# ReflowWiring.net
KiCad netlist of a schematic drawn in EAGLE
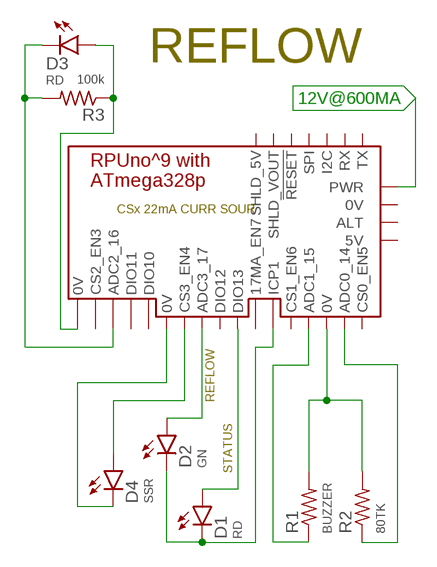
[diagram p0: schematic, sheet 1]

(export (version "E")
  (design (tool "Eeschema 10.0.6"))
  (components
    (comp (ref "BM1")
      (value "RPUNO")
      (footprint "eagle-import:NA-30")
      (libsource (lib "eagle-import") (part "RPUNO"))
    )
    (comp (ref "D1")
      (value "RD")
      (footprint "eagle-import:LED5MM")
      (libsource (lib "eagle-import") (part "LED5MM"))
    )
    (comp (ref "D2")
      (value "GN")
      (footprint "eagle-import:LED5MM")
      (libsource (lib "eagle-import") (part "LED5MM"))
    )
    (comp (ref "D3")
      (value "RD")
      (footprint "eagle-import:LED5MM")
      (libsource (lib "eagle-import") (part "LED5MM"))
    )
    (comp (ref "D4")
      (value "SSR")
      (footprint "eagle-import:LED5MM")
      (libsource (lib "eagle-import") (part "LED5MM"))
    )
    (comp (ref "R1")
      (value "BUZZER")
      (footprint "eagle-import:C0805(2012)")
      (libsource (lib "eagle-import") (part "R0805"))
    )
    (comp (ref "R2")
      (value "80TK")
      (footprint "eagle-import:C0805(2012)")
      (libsource (lib "eagle-import") (part "R0805"))
    )
    (comp (ref "R3")
      (value "100k")
      (footprint "eagle-import:C0805(2012)")
      (libsource (lib "eagle-import") (part "R0805"))
    )
  )
  (nets
    (net (code "1") (name "12V@600MA") (class "Default")
      (node (ref "BM1") (pin "8") (pinfunction "PWR_8") (pintype "bidirectional"))
    )
    (net (code "2") (name "Net-(BM1-0V-Pad26)") (class "Default")
      (node (ref "BM1") (pin "26") (pinfunction "0V_26") (pintype "bidirectional"))
      (node (ref "R1") (pin "2") (pinfunction "2_2") (pintype "passive"))
      (node (ref "R2") (pin "2") (pinfunction "2_2") (pintype "passive"))
    )
    (net (code "3") (name "Net-(BM1-0V-Pad27)") (class "Default")
      (node (ref "BM1") (pin "27") (pinfunction "0V_27") (pintype "bidirectional"))
      (node (ref "D3") (pin "A") (pinfunction "A_A") (pintype "passive"))
      (node (ref "R3") (pin "1") (pinfunction "1_1") (pintype "passive"))
    )
    (net (code "4") (name "Net-(BM1-0V-Pad28)") (class "Default")
      (node (ref "BM1") (pin "28") (pinfunction "0V_28") (pintype "bidirectional"))
      (node (ref "D4") (pin "K") (pinfunction "K_K") (pintype "passive"))
    )
    (net (code "5") (name "Net-(BM1-ADC0_14)") (class "Default")
      (node (ref "BM1") (pin "11") (pinfunction "ADC0_14_11") (pintype "bidirectional"))
      (node (ref "R2") (pin "1") (pinfunction "1_1") (pintype "passive"))
    )
    (net (code "6") (name "Net-(BM1-ADC1_15)") (class "Default")
      (node (ref "BM1") (pin "10") (pinfunction "ADC1_15_10") (pintype "bidirectional"))
      (node (ref "R1") (pin "1") (pinfunction "1_1") (pintype "passive"))
    )
    (net (code "7") (name "Net-(BM1-ADC2_16)") (class "Default")
      (node (ref "BM1") (pin "13") (pinfunction "ADC2_16_13") (pintype "bidirectional"))
      (node (ref "D3") (pin "K") (pinfunction "K_K") (pintype "passive"))
      (node (ref "R3") (pin "2") (pinfunction "2_2") (pintype "passive"))
    )
    (net (code "8") (name "Net-(BM1-ADC3_17)") (class "Default")
      (node (ref "BM1") (pin "16") (pinfunction "ADC3_17_16") (pintype "bidirectional"))
      (node (ref "D2") (pin "A") (pinfunction "A_A") (pintype "passive"))
    )
    (net (code "9") (name "Net-(BM1-CS3_EN4)") (class "Default")
      (node (ref "BM1") (pin "29") (pinfunction "CS3_EN4_29") (pintype "bidirectional"))
      (node (ref "D4") (pin "A") (pinfunction "A_A") (pintype "passive"))
    )
    (net (code "10") (name "Net-(BM1-DIO13)") (class "Default")
      (node (ref "BM1") (pin "18") (pinfunction "DIO13_18") (pintype "bidirectional"))
      (node (ref "D1") (pin "A") (pinfunction "A_A") (pintype "passive"))
    )
    (net (code "11") (name "Net-(BM1-ICP1)") (class "Default")
      (node (ref "BM1") (pin "12") (pinfunction "ICP1_12") (pintype "bidirectional"))
      (node (ref "D1") (pin "K") (pinfunction "K_K") (pintype "passive"))
      (node (ref "D2") (pin "K") (pinfunction "K_K") (pintype "passive"))
    )
    (net (code "12") (name "unconnected-(BM1-0V-Pad9)") (class "Default")
      (node (ref "BM1") (pin "9") (pinfunction "0V_9") (pintype "bidirectional"))
    )
    (net (code "13") (name "unconnected-(BM1-5V-Pad19)") (class "Default")
      (node (ref "BM1") (pin "19") (pinfunction "5V_19") (pintype "bidirectional"))
    )
    (net (code "14") (name "unconnected-(BM1-17MA_EN7-Pad21)") (class "Default")
      (node (ref "BM1") (pin "21") (pinfunction "17MA_EN7_21") (pintype "bidirectional"))
    )
    (net (code "15") (name "unconnected-(BM1-ALT-Pad20)") (class "Default")
      (node (ref "BM1") (pin "20") (pinfunction "ALT_20") (pintype "bidirectional"))
    )
    (net (code "16") (name "unconnected-(BM1-CS0_EN5-Pad23)") (class "Default")
      (node (ref "BM1") (pin "23") (pinfunction "CS0_EN5_23") (pintype "bidirectional"))
    )
    (net (code "17") (name "unconnected-(BM1-CS1_EN6-Pad22)") (class "Default")
      (node (ref "BM1") (pin "22") (pinfunction "CS1_EN6_22") (pintype "bidirectional"))
    )
    (net (code "18") (name "unconnected-(BM1-CS2_EN3-Pad24)") (class "Default")
      (node (ref "BM1") (pin "24") (pinfunction "CS2_EN3_24") (pintype "bidirectional"))
    )
    (net (code "19") (name "unconnected-(BM1-DIO10-Pad15)") (class "Default")
      (node (ref "BM1") (pin "15") (pinfunction "DIO10_15") (pintype "bidirectional"))
    )
    (net (code "20") (name "unconnected-(BM1-DIO11-Pad14)") (class "Default")
      (node (ref "BM1") (pin "14") (pinfunction "DIO11_14") (pintype "bidirectional"))
    )
    (net (code "21") (name "unconnected-(BM1-DIO12-Pad17)") (class "Default")
      (node (ref "BM1") (pin "17") (pinfunction "DIO12_17") (pintype "bidirectional"))
    )
    (net (code "22") (name "unconnected-(BM1-I2C-Pad3)") (class "Default")
      (node (ref "BM1") (pin "3") (pinfunction "I2C_3") (pintype "bidirectional"))
    )
    (net (code "23") (name "unconnected-(BM1-RX-Pad2)") (class "Default")
      (node (ref "BM1") (pin "2") (pinfunction "RX_2") (pintype "bidirectional"))
    )
    (net (code "24") (name "unconnected-(BM1-SHLD_5V-Pad6)") (class "Default")
      (node (ref "BM1") (pin "6") (pinfunction "SHLD_5V_6") (pintype "bidirectional"))
    )
    (net (code "25") (name "unconnected-(BM1-SHLD_VOUT-Pad7)") (class "Default")
      (node (ref "BM1") (pin "7") (pinfunction "SHLD_VOUT_7") (pintype "bidirectional"))
    )
    (net (code "26") (name "unconnected-(BM1-SPI-Pad4)") (class "Default")
      (node (ref "BM1") (pin "4") (pinfunction "SPI_4") (pintype "bidirectional"))
    )
    (net (code "27") (name "unconnected-(BM1-TX-Pad1)") (class "Default")
      (node (ref "BM1") (pin "1") (pinfunction "TX_1") (pintype "bidirectional"))
    )
    (net (code "28") (name "unconnected-(BM1-~{RESET}-Pad5)") (class "Default")
      (node (ref "BM1") (pin "5") (pinfunction "~{RESET}_5") (pintype "bidirectional"))
    )
  )
)
